# DC_Regulator.net
KiCad netlist of a schematic drawn in Altium Designer
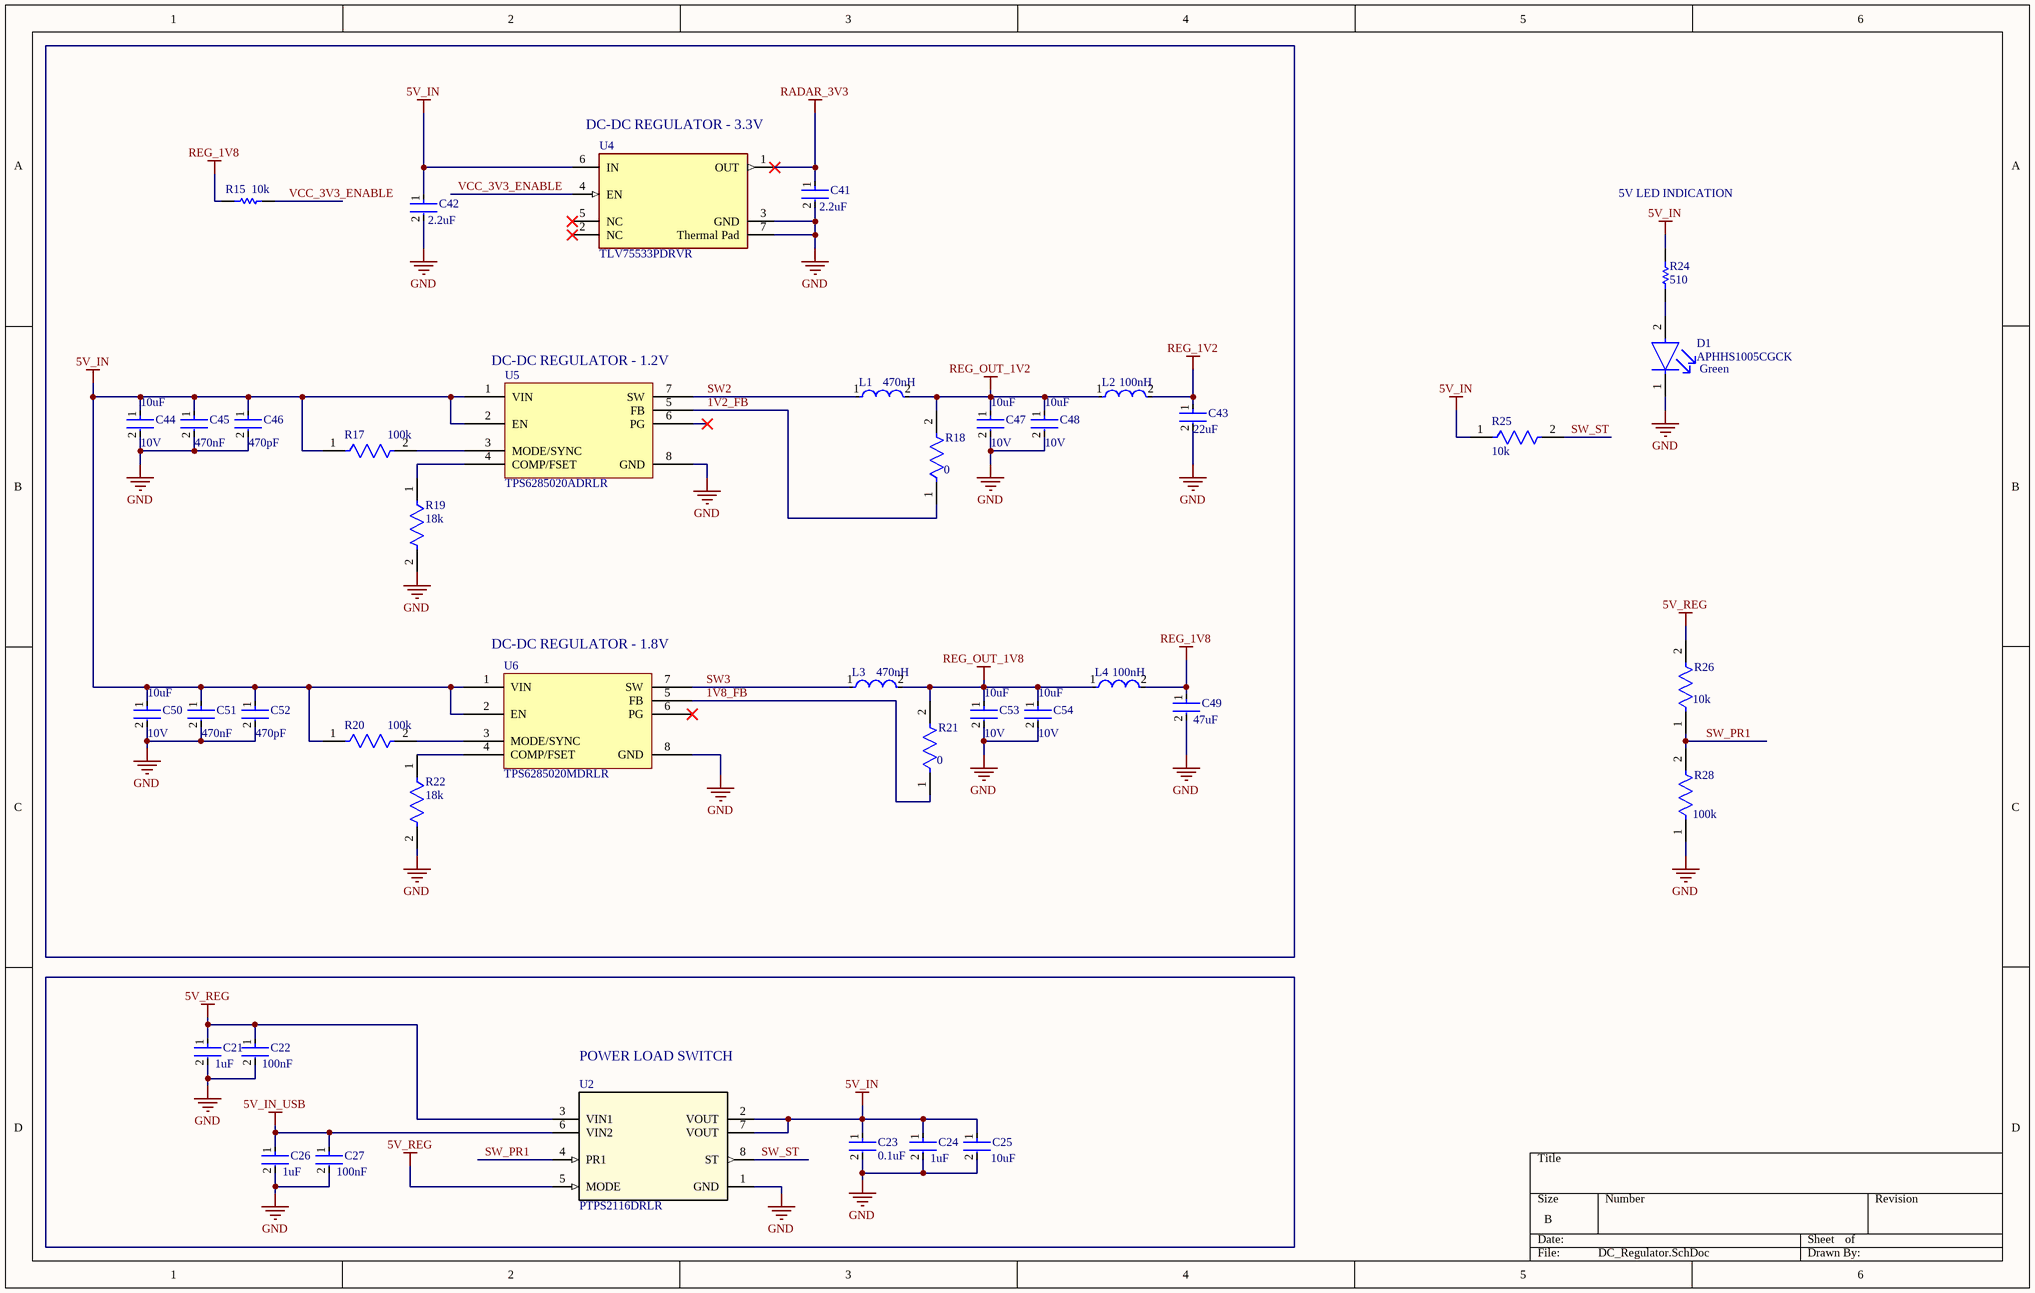
[diagram p0: DC_Regulator.SchDoc]

(export (version "E")
  (design (tool "Eeschema 10.0.6"))
  (components
    (comp (ref "C21")
      (value "GRT155C81A105KE01D")
      (footprint "FP-GRT155-0_05-IPC_B")
      (description "Multi-Layer Ceramic Capacitor 1uF 10V X6S ±10% 0402 Paper T/R")
      (fields (field (name "TOLERANCE") "10%") (field (name "CAPACITANCE") "1uF"))
      (libsource (lib "Altium Content Vault") (part "02cd4be3c70576c341d710602a673aa"))
    )
    (comp (ref "C22")
      (value "GCM155R71H104KE02D")
      (footprint "FP-GCM155-0_05-IPC_A")
      (description "Ceramic Capacitor for Automotive 100nF ±10% 50VDC X7R 0402 Paper T/R")
      (fields (field (name "CAPACITANCE") "100nF") (field (name "TOLERANCE") "10%"))
      (libsource (lib "Altium Content Vault") (part "02cd4be3c70576c341d710602a673aa"))
    )
    (comp (ref "C23")
      (value "0.1uF")
      (footprint "FP-C0402-BB-MFG")
      (description "CAP CER 0.1UF 10V X7R 0402")
      (fields
        (field (name "OCTOPART") "https://octopart.com/c0402c104k8ractu-kemet-106349")
        (field (name "MANUFACTURER PART NUMBER") "C0402C104K8RACTU")
      )
      (libsource (lib "Altium Content Vault") (part "b4654b650e69147ec39a6b967a45e02"))
    )
    (comp (ref "C24")
      (value "GRT155C81A105KE01D")
      (footprint "FP-GRT155-0_05-IPC_B")
      (description "Multi-Layer Ceramic Capacitor 1uF 10V X6S ±10% 0402 Paper T/R")
      (fields (field (name "TOLERANCE") "10%") (field (name "CAPACITANCE") "1uF"))
      (libsource (lib "Altium Content Vault") (part "02cd4be3c70576c341d710602a673aa"))
    )
    (comp (ref "C25")
      (value "10uF")
      (footprint "FP-GRM188-0_2-IPC_B")
      (description "Chip Multilayer Ceramic Capacitors for General Purpose, 0603, 10uF, X7R, 15%, 20%, 10V")
      (fields (field (name "Comment") "GRM188Z71A106MA73D"))
      (libsource (lib "Altium Content Vault") (part "11868f565c42a9108669ba33697ecf6"))
    )
    (comp (ref "C26")
      (value "GRT155C81A105KE01D")
      (footprint "FP-GRT155-0_05-IPC_B")
      (description "Multi-Layer Ceramic Capacitor 1uF 10V X6S ±10% 0402 Paper T/R")
      (fields (field (name "TOLERANCE") "10%") (field (name "CAPACITANCE") "1uF"))
      (libsource (lib "Altium Content Vault") (part "02cd4be3c70576c341d710602a673aa"))
    )
    (comp (ref "C27")
      (value "GCM155R71H104KE02D")
      (footprint "FP-GCM155-0_05-IPC_A")
      (description "Ceramic Capacitor for Automotive 100nF ±10% 50VDC X7R 0402 Paper T/R")
      (fields (field (name "CAPACITANCE") "100nF") (field (name "TOLERANCE") "10%"))
      (libsource (lib "Altium Content Vault") (part "02cd4be3c70576c341d710602a673aa"))
    )
    (comp (ref "C41")
      (value "GRM155C81C225KE11D")
      (footprint "FP-GRM155-0_2-MFG")
      (description "Chip Multilayer Ceramic Capacitors for General Purpose, 0402, 2.2uF, X6S, 22%, 10%, 16V")
      (fields (field (name "TOLERANCE") "10%") (field (name "CAPACITANCE") "2.2uF"))
      (libsource (lib "Altium Content Vault") (part "b4654b650e69147ec39a6b967a45e02"))
    )
    (comp (ref "C42")
      (value "GRM155C81C225KE11D")
      (footprint "FP-GRM155-0_2-MFG")
      (description "Chip Multilayer Ceramic Capacitors for General Purpose, 0402, 2.2uF, X6S, 22%, 10%, 16V")
      (fields (field (name "TOLERANCE") "10%") (field (name "CAPACITANCE") "2.2uF"))
      (libsource (lib "Altium Content Vault") (part "b4654b650e69147ec39a6b967a45e02"))
    )
    (comp (ref "C43")
      (value "GRM31CR70J226ME19K")
      (footprint "FP-GRM31C-0_2-e0_3_0_8-MFG")
      (description "Chip Multilayer Ceramic Capacitors for General Purpose, 1206, 22uF, X7R, 15%, 20%, 6.3V")
      (fields (field (name "TOLERANCE") "20%") (field (name "CAPACITANCE") "22uF"))
      (libsource (lib "Altium Content Vault") (part "02cd4be3c70576c341d710602a673aa"))
    )
    (comp (ref "C44")
      (value "GRM188C81A106MA73D")
      (footprint "FP-GRM188-0_2-MFG")
      (description "Chip Multilayer Ceramic Capacitors for General Purpose, 0603, 10uF, X6S, 22%, 20%, 10V")
      (fields
        (field (name "VOLTAGE RATING (DC)") "10V")
        (field (name "TOLERANCE") "20%")
        (field (name "CAPACITANCE") "10uF")
      )
      (libsource (lib "Altium Content Vault") (part "11868f565c42a9108669ba33697ecf6"))
    )
    (comp (ref "C45")
      (value "GRM188R71C474KA88D")
      (footprint "FP-GRM188-0_1-e0_2_0_5-IPC_B")
      (description "Chip Multilayer Ceramic Capacitors for General Purpose, 0603, 0.47uF, X7R, 15%, 10%, 16V")
      (fields
        (field (name "CAPACITANCE") "470nF")
        (field (name "VOLTAGE") "16V")
        (field (name "TOLERANCE") "10%")
      )
      (libsource (lib "Altium Content Vault") (part "11868f565c42a9108669ba33697ecf6"))
    )
    (comp (ref "C46")
      (value "GRM1555C1H471JA01D")
      (footprint "FP-GRM155-0_05-IPC_A")
      (description "Chip Multilayer Ceramic Capacitors for General Purpose, 0402, 470pF, C0G, 30ppm/°C, 5%, 50V")
      (fields
        (field (name "VOLTAGE") "50V")
        (field (name "TOLERANCE") "5%")
        (field (name "CAPACITANCE") "470pF")
      )
      (libsource (lib "Altium Content Vault") (part "02cd4be3c70576c341d710602a673aa"))
    )
    (comp (ref "C47")
      (value "GRM188C81A106MA73D")
      (footprint "FP-GRM188-0_2-MFG")
      (description "Chip Multilayer Ceramic Capacitors for General Purpose, 0603, 10uF, X6S, 22%, 20%, 10V")
      (fields
        (field (name "VOLTAGE RATING (DC)") "10V")
        (field (name "TOLERANCE") "20%")
        (field (name "CAPACITANCE") "10uF")
      )
      (libsource (lib "Altium Content Vault") (part "11868f565c42a9108669ba33697ecf6"))
    )
    (comp (ref "C48")
      (value "GRM188C81A106MA73D")
      (footprint "FP-GRM188-0_2-MFG")
      (description "Chip Multilayer Ceramic Capacitors for General Purpose, 0603, 10uF, X6S, 22%, 20%, 10V")
      (fields
        (field (name "VOLTAGE RATING (DC)") "10V")
        (field (name "TOLERANCE") "20%")
        (field (name "CAPACITANCE") "10uF")
      )
      (libsource (lib "Altium Content Vault") (part "11868f565c42a9108669ba33697ecf6"))
    )
    (comp (ref "C49")
      (value "GRM31CR60J476ME19L")
      (footprint "FP-GRM31C-0_2-e0_3_0_8-IPC_C")
      (description "Chip Multilayer Ceramic Capacitors for General Purpose, 1206, 47uF, X5R, 15%, 20%, 6.3V")
      (fields
        (field (name "TOLERANCE") "20%")
        (field (name "VOLTAGE") "6.3V")
        (field (name "CAPACITANCE") "47uF")
      )
      (libsource (lib "Altium Content Vault") (part "02cd4be3c70576c341d710602a673aa"))
    )
    (comp (ref "C50")
      (value "GRM188C81A106MA73D")
      (footprint "FP-GRM188-0_2-MFG")
      (description "Chip Multilayer Ceramic Capacitors for General Purpose, 0603, 10uF, X6S, 22%, 20%, 10V")
      (fields
        (field (name "VOLTAGE RATING (DC)") "10V")
        (field (name "TOLERANCE") "20%")
        (field (name "CAPACITANCE") "10uF")
      )
      (libsource (lib "Altium Content Vault") (part "11868f565c42a9108669ba33697ecf6"))
    )
    (comp (ref "C51")
      (value "GRM188R71C474KA88D")
      (footprint "FP-GRM188-0_1-e0_2_0_5-IPC_B")
      (description "Chip Multilayer Ceramic Capacitors for General Purpose, 0603, 0.47uF, X7R, 15%, 10%, 16V")
      (fields
        (field (name "CAPACITANCE") "470nF")
        (field (name "VOLTAGE") "16V")
        (field (name "TOLERANCE") "10%")
      )
      (libsource (lib "Altium Content Vault") (part "11868f565c42a9108669ba33697ecf6"))
    )
    (comp (ref "C52")
      (value "GRM1555C1H471JA01D")
      (footprint "FP-GRM155-0_05-IPC_A")
      (description "Chip Multilayer Ceramic Capacitors for General Purpose, 0402, 470pF, C0G, 30ppm/°C, 5%, 50V")
      (fields
        (field (name "VOLTAGE") "50V")
        (field (name "TOLERANCE") "5%")
        (field (name "CAPACITANCE") "470pF")
      )
      (libsource (lib "Altium Content Vault") (part "02cd4be3c70576c341d710602a673aa"))
    )
    (comp (ref "C53")
      (value "GRM188C81A106MA73D")
      (footprint "FP-GRM188-0_2-MFG")
      (description "Chip Multilayer Ceramic Capacitors for General Purpose, 0603, 10uF, X6S, 22%, 20%, 10V")
      (fields
        (field (name "VOLTAGE RATING (DC)") "10V")
        (field (name "TOLERANCE") "20%")
        (field (name "CAPACITANCE") "10uF")
      )
      (libsource (lib "Altium Content Vault") (part "11868f565c42a9108669ba33697ecf6"))
    )
    (comp (ref "C54")
      (value "GRM188C81A106MA73D")
      (footprint "FP-GRM188-0_2-MFG")
      (description "Chip Multilayer Ceramic Capacitors for General Purpose, 0603, 10uF, X6S, 22%, 20%, 10V")
      (fields
        (field (name "VOLTAGE RATING (DC)") "10V")
        (field (name "TOLERANCE") "20%")
        (field (name "CAPACITANCE") "10uF")
      )
      (libsource (lib "Altium Content Vault") (part "11868f565c42a9108669ba33697ecf6"))
    )
    (comp (ref "D1")
      (value "APHHS1005CGCK")
      (footprint "FP-APHHS1005CGCK-MFG")
      (description "LED GREEN CLEAR CHIP SMD")
      (fields (field (name "ILLUMINATION COLOR") "Green"))
      (libsource (lib "Altium Content Vault") (part "8706943c75ba83719d021d2fdc84c58"))
    )
    (comp (ref "L1")
      (value "470nH")
      (footprint "FP-DFE201210U-MFG")
      (description "FIXED IND .47UH 3.0A 42MOHM")
      (libsource (lib "Altium Content Vault") (part "725321dda6339637d4d059423bc1c3c"))
    )
    (comp (ref "L2")
      (value "100nH")
      (footprint "FP-LQM2MPZ_JH-w2_4-MFG")
      (description "FIXED IND 0.1UH 4000MA INFOTMT,")
      (libsource (lib "Altium Content Vault") (part "725321dda6339637d4d059423bc1c3c"))
    )
    (comp (ref "L3")
      (value "470nH")
      (footprint "FP-DFE201210U-MFG")
      (description "FIXED IND .47UH 3.0A 42MOHM")
      (libsource (lib "Altium Content Vault") (part "725321dda6339637d4d059423bc1c3c"))
    )
    (comp (ref "L4")
      (value "100nH")
      (footprint "FP-LQM2MPZ_JH-w2_4-MFG")
      (description "FIXED IND 0.1UH 4000MA INFOTMT,")
      (libsource (lib "Altium Content Vault") (part "725321dda6339637d4d059423bc1c3c"))
    )
    (comp (ref "R15")
      (value "10k")
      (footprint "RESC1005X40X25LL05T10")
      (fields (field (name "PART NUMBER") "RC0402FR-0710KL") (field (name "MANUFACTURER") "Yageo / Phycomp"))
      (libsource (lib "Altium Content Vault") (part "RES"))
    )
    (comp (ref "R17")
      (value "CRCW0402100KFKEDC")
      (footprint "FP-CRCW0402-C-e3-MFG")
      (description "RES 100K OHM 1% 1/16W 0402")
      (fields (field (name "TOLERANCE") "1%") (field (name "RESISTANCE") "100k"))
      (libsource (lib "Altium Content Vault") (part "1029c3af85768c4190bb7ad29bc67b5"))
    )
    (comp (ref "R18")
      (value "RC0402JR-070RP")
      (footprint "FP-RC0402-0_4-MFG")
      (description "RES SMD 0 OHM JUMPER 1/16W 0402")
      (fields (field (name "RESISTANCE") "0"))
      (libsource (lib "Altium Content Vault") (part "1029c3af85768c4190bb7ad29bc67b5"))
    )
    (comp (ref "R19")
      (value "CRCW040218K0FKEDC")
      (footprint "FP-CRCW0402-e3-MFG")
      (description "RES 18K OHM 1% 1/16W 0402")
      (fields (field (name "RESISTANCE") "18k") (field (name "TOLERANCE") "1%"))
      (libsource (lib "Altium Content Vault") (part "1029c3af85768c4190bb7ad29bc67b5"))
    )
    (comp (ref "R20")
      (value "CRCW0402100KFKEDC")
      (footprint "FP-CRCW0402-C-e3-MFG")
      (description "RES 100K OHM 1% 1/16W 0402")
      (fields (field (name "TOLERANCE") "1%") (field (name "RESISTANCE") "100k"))
      (libsource (lib "Altium Content Vault") (part "1029c3af85768c4190bb7ad29bc67b5"))
    )
    (comp (ref "R21")
      (value "RC0402JR-070RP")
      (footprint "FP-RC0402-0_4-MFG")
      (description "RES SMD 0 OHM JUMPER 1/16W 0402")
      (fields (field (name "RESISTANCE") "0"))
      (libsource (lib "Altium Content Vault") (part "1029c3af85768c4190bb7ad29bc67b5"))
    )
    (comp (ref "R22")
      (value "CRCW040218K0FKEDC")
      (footprint "FP-CRCW0402-e3-MFG")
      (description "RES 18K OHM 1% 1/16W 0402")
      (fields (field (name "RESISTANCE") "18k") (field (name "TOLERANCE") "1%"))
      (libsource (lib "Altium Content Vault") (part "1029c3af85768c4190bb7ad29bc67b5"))
    )
    (comp (ref "R24")
      (value "510")
      (footprint "RESC1005X40X25NL05T05")
      (fields (field (name "MANUFACTURER") "Panasonic") (field (name "PART NUMBER") "ERJ-2GEJ511X"))
      (libsource (lib "Altium Content Vault") (part "RES"))
    )
    (comp (ref "R25")
      (value "CRCW040210K0FKEDC")
      (footprint "FP-CRCW0402-C-e3-IPC_C")
      (description "RES 10K OHM 1% 1/16W 0402")
      (fields (field (name "TOLERANCE") "1%") (field (name "RESISTANCE") "10k"))
      (libsource (lib "Altium Content Vault") (part "1029c3af85768c4190bb7ad29bc67b5"))
    )
    (comp (ref "R26")
      (value "CRCW040210K0FKEDC")
      (footprint "FP-CRCW0402-C-e3-IPC_C")
      (description "RES 10K OHM 1% 1/16W 0402")
      (fields (field (name "TOLERANCE") "1%") (field (name "RESISTANCE") "10k"))
      (libsource (lib "Altium Content Vault") (part "1029c3af85768c4190bb7ad29bc67b5"))
    )
    (comp (ref "R28")
      (value "CRCW0402100KFKED")
      (footprint "FP-CRCW0402-e3-IPC_C")
      (description "RES Thick Film, 100kΩ, 1%, 0.063W, 100ppm/°C, 0402")
      (fields (field (name "RESISTANCE") "100k") (field (name "TOLERANCE") "1%"))
      (libsource (lib "Altium Content Vault") (part "1029c3af85768c4190bb7ad29bc67b5"))
    )
    (comp (ref "U2")
      (value "PTPS2116DRLR")
      (footprint "DRL0008A-MFG")
      (description "1.6-V to 5.5-V, 40-mâ„¦, 2.5-A, low-IQ, priority power multiplexer ; 8-SOT-5X3 -40 to 125")
      (fields (field (name "COPYRIGHT") "Copyright (C) 2025 Ultra Librarian. All rights reserved."))
      (libsource (lib "PTPS2116DRLR") (part "PTPS2116DRLR"))
    )
    (comp (ref "U4")
      (value "TLV75533PDRVR")
      (footprint "FP-DRV0006A-IPC_A")
      (description "IC REG LINEAR 3.3V 500MA 6WSON")
      (libsource (lib "Altium Content Vault") (part "cca53198dfe000ec5429f13d2cbe4e1"))
    )
    (comp (ref "U5")
      (value "TPS6285020ADRLR")
      (footprint "TPS6285020ADRLR")
      (fields (field (name "MANUFACTURER") "Texas Instruments"))
      (libsource (lib "Schlib1") (part "TPS6285020ADRLR"))
    )
    (comp (ref "U6")
      (value "TPS6285020MDRLR")
      (footprint "TPS6285020MDRLR")
      (fields (field (name "MANUFACTURER") "Texas Instruments"))
      (libsource (lib "Schlib1") (part "TPS6285020MDRLR"))
    )
  )
  (nets
    (net (code "1") (name "/1V2_FB") (class "Default")
      (node (ref "R18") (pin "1") (pinfunction "1_1") (pintype "passive"))
      (node (ref "U5") (pin "5") (pinfunction "FB_5") (pintype "passive"))
    )
    (net (code "2") (name "/1V8_FB") (class "Default")
      (node (ref "R21") (pin "1") (pinfunction "1_1") (pintype "passive"))
      (node (ref "U6") (pin "5") (pinfunction "FB_5") (pintype "passive"))
    )
    (net (code "3") (name "/SW2") (class "Default")
      (node (ref "L1") (pin "1") (pinfunction "1_1") (pintype "passive"))
      (node (ref "U5") (pin "7") (pinfunction "SW_7") (pintype "passive"))
    )
    (net (code "4") (name "/SW3") (class "Default")
      (node (ref "L3") (pin "1") (pinfunction "1_1") (pintype "passive"))
      (node (ref "U6") (pin "7") (pinfunction "SW_7") (pintype "passive"))
    )
    (net (code "5") (name "/SW_PR1") (class "Default")
      (node (ref "R26") (pin "1") (pinfunction "1_1") (pintype "passive"))
      (node (ref "R28") (pin "2") (pinfunction "2_2") (pintype "passive"))
      (node (ref "U2") (pin "4") (pinfunction "PR1_4") (pintype "input"))
    )
    (net (code "6") (name "/SW_ST") (class "Default")
      (node (ref "R25") (pin "2") (pinfunction "2_2") (pintype "passive"))
      (node (ref "U2") (pin "8") (pinfunction "ST_8") (pintype "output"))
    )
    (net (code "7") (name "/VCC_3V3_ENABLE") (class "Default")
      (node (ref "R15") (pin "2") (pinfunction "2_2") (pintype "passive"))
      (node (ref "U4") (pin "4") (pinfunction "EN_4") (pintype "input"))
    )
    (net (code "8") (name "5V_IN") (class "Default")
      (node (ref "C23") (pin "1") (pinfunction "1_1") (pintype "passive"))
      (node (ref "C24") (pin "1") (pinfunction "1_1") (pintype "passive"))
      (node (ref "C25") (pin "1") (pinfunction "1_1") (pintype "passive"))
      (node (ref "C42") (pin "1") (pinfunction "1_1") (pintype "passive"))
      (node (ref "C44") (pin "1") (pinfunction "1_1") (pintype "passive"))
      (node (ref "C45") (pin "1") (pinfunction "1_1") (pintype "passive"))
      (node (ref "C46") (pin "1") (pinfunction "1_1") (pintype "passive"))
      (node (ref "C50") (pin "1") (pinfunction "1_1") (pintype "passive"))
      (node (ref "C51") (pin "1") (pinfunction "1_1") (pintype "passive"))
      (node (ref "C52") (pin "1") (pinfunction "1_1") (pintype "passive"))
      (node (ref "R17") (pin "1") (pinfunction "1_1") (pintype "passive"))
      (node (ref "R20") (pin "1") (pinfunction "1_1") (pintype "passive"))
      (node (ref "R24") (pin "2") (pinfunction "2_2") (pintype "passive"))
      (node (ref "R25") (pin "1") (pinfunction "1_1") (pintype "passive"))
      (node (ref "U2") (pin "2") (pinfunction "VOUT_2") (pintype "passive"))
      (node (ref "U2") (pin "7") (pinfunction "VOUT_7") (pintype "passive"))
      (node (ref "U4") (pin "6") (pinfunction "IN_6") (pintype "power_in"))
      (node (ref "U5") (pin "1") (pinfunction "VIN_1") (pintype "passive"))
      (node (ref "U5") (pin "2") (pinfunction "EN_2") (pintype "passive"))
      (node (ref "U6") (pin "1") (pinfunction "VIN_1") (pintype "passive"))
      (node (ref "U6") (pin "2") (pinfunction "EN_2") (pintype "passive"))
    )
    (net (code "9") (name "5V_IN_USB") (class "Default")
      (node (ref "C26") (pin "1") (pinfunction "1_1") (pintype "passive"))
      (node (ref "C27") (pin "1") (pinfunction "1_1") (pintype "passive"))
      (node (ref "U2") (pin "6") (pinfunction "VIN2_6") (pintype "power_in"))
    )
    (net (code "10") (name "5V_REG") (class "Default")
      (node (ref "C21") (pin "1") (pinfunction "1_1") (pintype "passive"))
      (node (ref "C22") (pin "1") (pinfunction "1_1") (pintype "passive"))
      (node (ref "R26") (pin "2") (pinfunction "2_2") (pintype "passive"))
      (node (ref "U2") (pin "3") (pinfunction "VIN1_3") (pintype "power_in"))
      (node (ref "U2") (pin "5") (pinfunction "MODE_5") (pintype "input"))
    )
    (net (code "11") (name "GND") (class "Default")
      (node (ref "C21") (pin "2") (pinfunction "2_2") (pintype "passive"))
      (node (ref "C22") (pin "2") (pinfunction "2_2") (pintype "passive"))
      (node (ref "C23") (pin "2") (pinfunction "2_2") (pintype "passive"))
      (node (ref "C24") (pin "2") (pinfunction "2_2") (pintype "passive"))
      (node (ref "C25") (pin "2") (pinfunction "2_2") (pintype "passive"))
      (node (ref "C26") (pin "2") (pinfunction "2_2") (pintype "passive"))
      (node (ref "C27") (pin "2") (pinfunction "2_2") (pintype "passive"))
      (node (ref "C41") (pin "2") (pinfunction "2_2") (pintype "passive"))
      (node (ref "C42") (pin "2") (pinfunction "2_2") (pintype "passive"))
      (node (ref "C43") (pin "2") (pinfunction "2_2") (pintype "passive"))
      (node (ref "C44") (pin "2") (pinfunction "2_2") (pintype "passive"))
      (node (ref "C45") (pin "2") (pinfunction "2_2") (pintype "passive"))
      (node (ref "C46") (pin "2") (pinfunction "2_2") (pintype "passive"))
      (node (ref "C47") (pin "2") (pinfunction "2_2") (pintype "passive"))
      (node (ref "C48") (pin "2") (pinfunction "2_2") (pintype "passive"))
      (node (ref "C49") (pin "2") (pinfunction "2_2") (pintype "passive"))
      (node (ref "C50") (pin "2") (pinfunction "2_2") (pintype "passive"))
      (node (ref "C51") (pin "2") (pinfunction "2_2") (pintype "passive"))
      (node (ref "C52") (pin "2") (pinfunction "2_2") (pintype "passive"))
      (node (ref "C53") (pin "2") (pinfunction "2_2") (pintype "passive"))
      (node (ref "C54") (pin "2") (pinfunction "2_2") (pintype "passive"))
      (node (ref "D1") (pin "1") (pinfunction "C_1") (pintype "passive"))
      (node (ref "R19") (pin "2") (pinfunction "2_2") (pintype "passive"))
      (node (ref "R22") (pin "2") (pinfunction "2_2") (pintype "passive"))
      (node (ref "R28") (pin "1") (pinfunction "1_1") (pintype "passive"))
      (node (ref "U2") (pin "1") (pinfunction "GND_1") (pintype "power_in"))
      (node (ref "U4") (pin "3") (pinfunction "GND_3") (pintype "power_in"))
      (node (ref "U4") (pin "7") (pinfunction "Thermal_Pad_7") (pintype "power_in"))
      (node (ref "U5") (pin "8") (pinfunction "GND_8") (pintype "passive"))
      (node (ref "U6") (pin "8") (pinfunction "GND_8") (pintype "passive"))
    )
    (net (code "12") (name "Net-(D1-A)") (class "Default")
      (node (ref "D1") (pin "2") (pinfunction "A_2") (pintype "passive"))
      (node (ref "R24") (pin "1") (pinfunction "1_1") (pintype "passive"))
    )
    (net (code "13") (name "Net-(U5-COMP{slash}FSET)") (class "Default")
      (node (ref "R19") (pin "1") (pinfunction "1_1") (pintype "passive"))
      (node (ref "U5") (pin "4") (pinfunction "COMP/FSET_4") (pintype "passive"))
    )
    (net (code "14") (name "Net-(U5-MODE{slash}SYNC)") (class "Default")
      (node (ref "R17") (pin "2") (pinfunction "2_2") (pintype "passive"))
      (node (ref "U5") (pin "3") (pinfunction "MODE/SYNC_3") (pintype "passive"))
    )
    (net (code "15") (name "Net-(U6-COMP{slash}FSET)") (class "Default")
      (node (ref "R22") (pin "1") (pinfunction "1_1") (pintype "passive"))
      (node (ref "U6") (pin "4") (pinfunction "COMP/FSET_4") (pintype "passive"))
    )
    (net (code "16") (name "Net-(U6-MODE{slash}SYNC)") (class "Default")
      (node (ref "R20") (pin "2") (pinfunction "2_2") (pintype "passive"))
      (node (ref "U6") (pin "3") (pinfunction "MODE/SYNC_3") (pintype "passive"))
    )
    (net (code "17") (name "RADAR_3V3") (class "Default")
      (node (ref "C41") (pin "1") (pinfunction "1_1") (pintype "passive"))
      (node (ref "U4") (pin "1") (pinfunction "OUT_1") (pintype "output"))
    )
    (net (code "18") (name "REG_1V2") (class "Default")
      (node (ref "C43") (pin "1") (pinfunction "1_1") (pintype "passive"))
      (node (ref "L2") (pin "2") (pinfunction "2_2") (pintype "passive"))
    )
    (net (code "19") (name "REG_1V8") (class "Default")
      (node (ref "C49") (pin "1") (pinfunction "1_1") (pintype "passive"))
      (node (ref "L4") (pin "2") (pinfunction "2_2") (pintype "passive"))
      (node (ref "R15") (pin "1") (pinfunction "1_1") (pintype "passive"))
    )
    (net (code "20") (name "REG_OUT_1V2") (class "Default")
      (node (ref "C47") (pin "1") (pinfunction "1_1") (pintype "passive"))
      (node (ref "C48") (pin "1") (pinfunction "1_1") (pintype "passive"))
      (node (ref "L1") (pin "2") (pinfunction "2_2") (pintype "passive"))
      (node (ref "L2") (pin "1") (pinfunction "1_1") (pintype "passive"))
      (node (ref "R18") (pin "2") (pinfunction "2_2") (pintype "passive"))
    )
    (net (code "21") (name "REG_OUT_1V8") (class "Default")
      (node (ref "C53") (pin "1") (pinfunction "1_1") (pintype "passive"))
      (node (ref "C54") (pin "1") (pinfunction "1_1") (pintype "passive"))
      (node (ref "L3") (pin "2") (pinfunction "2_2") (pintype "passive"))
      (node (ref "L4") (pin "1") (pinfunction "1_1") (pintype "passive"))
      (node (ref "R21") (pin "2") (pinfunction "2_2") (pintype "passive"))
    )
    (net (code "22") (name "unconnected-(U4-NC-Pad2)") (class "Default")
      (node (ref "U4") (pin "2") (pinfunction "NC_2") (pintype "passive+no_connect"))
    )
    (net (code "23") (name "unconnected-(U4-NC-Pad5)") (class "Default")
      (node (ref "U4") (pin "5") (pinfunction "NC_5") (pintype "passive+no_connect"))
    )
    (net (code "24") (name "unconnected-(U5-PG-Pad6)") (class "Default")
      (node (ref "U5") (pin "6") (pinfunction "PG_6") (pintype "passive+no_connect"))
    )
    (net (code "25") (name "unconnected-(U6-PG-Pad6)") (class "Default")
      (node (ref "U6") (pin "6") (pinfunction "PG_6") (pintype "passive+no_connect"))
    )
  )
)
